# V1_1.net
KiCad netlist of a schematic drawn in Altium Designer
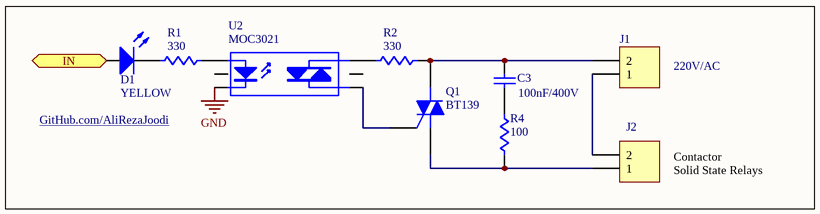
[diagram p0: V1.1.SchDoc]

(export (version "E")
  (design (tool "Eeschema 10.0.6"))
  (components
    (comp (ref "C3")
      (value "100nF/400V")
      (footprint "CAPR7.62-6.8x5")
      (description "Capacitor")
      (fields (field (name "MANUFACTURER") "Generic Components") (field (name "PUBLISHER") "Altium Limited"))
      (libsource (lib "Miscellaneous Devices") (part "Cap"))
    )
    (comp (ref "D1")
      (value "YELLOW")
      (footprint "LED-5mm_Red")
      (description "Typical INFRARED GaAs LED")
      (fields (field (name "MANUFACTURER") "Generic Components") (field (name "PUBLISHER") "Altium Limited"))
      (libsource (lib "Miscellaneous Devices") (part "LED"))
    )
    (comp (ref "J1")
      (value "2PIN")
      (footprint "Fonics_2PIN_1")
      (description "Header, 2-Pin")
      (fields (field (name "PUBLISHER") "Altium Limited"))
      (libsource (lib "Miscellaneous Connectors") (part "Header 2"))
    )
    (comp (ref "J2")
      (value "2PIN")
      (footprint "Fonics_2PIN_1")
      (description "Header, 2-Pin")
      (fields (field (name "PUBLISHER") "Altium Limited"))
      (libsource (lib "Miscellaneous Connectors") (part "Header 2"))
    )
    (comp (ref "Q1")
      (value "BT139")
      (footprint "TO220V")
      (description "Silicon Bidirectional Triode Thyristor")
      (fields (field (name "MANUFACTURER") "Generic Components") (field (name "PUBLISHER") "Altium Limited"))
      (libsource (lib "Miscellaneous Devices") (part "Triac"))
    )
    (comp (ref "R1")
      (value "330")
      (footprint "AXIAL-0.4")
      (description "Resistor")
      (fields (field (name "MANUFACTURER") "Generic Components") (field (name "PUBLISHER") "Altium Limited"))
      (libsource (lib "Miscellaneous Devices") (part "Res1"))
    )
    (comp (ref "R2")
      (value "330")
      (footprint "AXIAL-0.4")
      (description "Resistor")
      (fields (field (name "MANUFACTURER") "Generic Components") (field (name "PUBLISHER") "Altium Limited"))
      (libsource (lib "Miscellaneous Devices") (part "Res1"))
    )
    (comp (ref "R4")
      (value "100")
      (footprint "AXIAL-0.4")
      (description "Resistor")
      (fields (field (name "MANUFACTURER") "Generic Components") (field (name "PUBLISHER") "Altium Limited"))
      (libsource (lib "Miscellaneous Devices") (part "Res1"))
    )
    (comp (ref "U2")
      (value "MOC3021")
      (footprint "DIP-6")
      (description "Opto-Triac")
      (fields
        (field (name "PUBLISHER") "www.picpars.com")
        (field (name "DESIGNER") "Seyed Mohsen Ghasemian")
        (field (name "E-MAIL") "picpars@gmail.com")
      )
      (libsource (lib "PicPars.com_usefully_Library") (part "MOC3021-3"))
    )
  )
  (nets
    (net (code "1") (name "/IN") (class "Default")
      (node (ref "D1") (pin "1") (pinfunction "A_1") (pintype "passive"))
    )
    (net (code "2") (name "GND") (class "Default")
      (node (ref "U2") (pin "2") (pinfunction "K_2") (pintype "passive"))
    )
    (net (code "3") (name "Net-(C3-Pad1)") (class "Default")
      (node (ref "C3") (pin "1") (pinfunction "1_1") (pintype "passive"))
      (node (ref "R4") (pin "2") (pinfunction "2_2") (pintype "passive"))
    )
    (net (code "4") (name "Net-(D1-K)") (class "Default")
      (node (ref "D1") (pin "2") (pinfunction "K_2") (pintype "passive"))
      (node (ref "R1") (pin "1") (pinfunction "1_1") (pintype "passive"))
    )
    (net (code "5") (name "Net-(J1-Pad1)") (class "Default")
      (node (ref "J1") (pin "1") (pinfunction "1_1") (pintype "passive"))
      (node (ref "J2") (pin "2") (pinfunction "2_2") (pintype "passive"))
    )
    (net (code "6") (name "Net-(Q1-G)") (class "Default")
      (node (ref "Q1") (pin "3") (pinfunction "G_3") (pintype "passive"))
      (node (ref "U2") (pin "6") (pinfunction "A/K_6") (pintype "passive"))
    )
    (net (code "7") (name "Net-(Q1-M1)") (class "Default")
      (node (ref "J2") (pin "1") (pinfunction "1_1") (pintype "passive"))
      (node (ref "Q1") (pin "1") (pinfunction "M1_1") (pintype "passive"))
      (node (ref "R4") (pin "1") (pinfunction "1_1") (pintype "passive"))
    )
    (net (code "8") (name "Net-(Q1-M2)") (class "Default")
      (node (ref "C3") (pin "2") (pinfunction "2_2") (pintype "passive"))
      (node (ref "J1") (pin "2") (pinfunction "2_2") (pintype "passive"))
      (node (ref "Q1") (pin "2") (pinfunction "M2_2") (pintype "passive"))
      (node (ref "R2") (pin "2") (pinfunction "2_2") (pintype "passive"))
    )
    (net (code "9") (name "Net-(R2-Pad1)") (class "Default")
      (node (ref "R2") (pin "1") (pinfunction "1_1") (pintype "passive"))
      (node (ref "U2") (pin "4") (pinfunction "A/K_4") (pintype "passive"))
    )
    (net (code "10") (name "Net-(U2-A)") (class "Default")
      (node (ref "R1") (pin "2") (pinfunction "2_2") (pintype "passive"))
      (node (ref "U2") (pin "1") (pinfunction "A_1") (pintype "passive"))
    )
    (net (code "11") (name "unconnected-(U2-NC-Pad3)") (class "Default")
      (node (ref "U2") (pin "3") (pinfunction "NC_3") (pintype "passive"))
    )
    (net (code "12") (name "unconnected-(U2-NC-Pad5)") (class "Default")
      (node (ref "U2") (pin "5") (pinfunction "NC_5") (pintype "passive"))
    )
  )
)
